# mistral_humtemp_breakout0.net
KiCad netlist of a schematic drawn in EAGLE
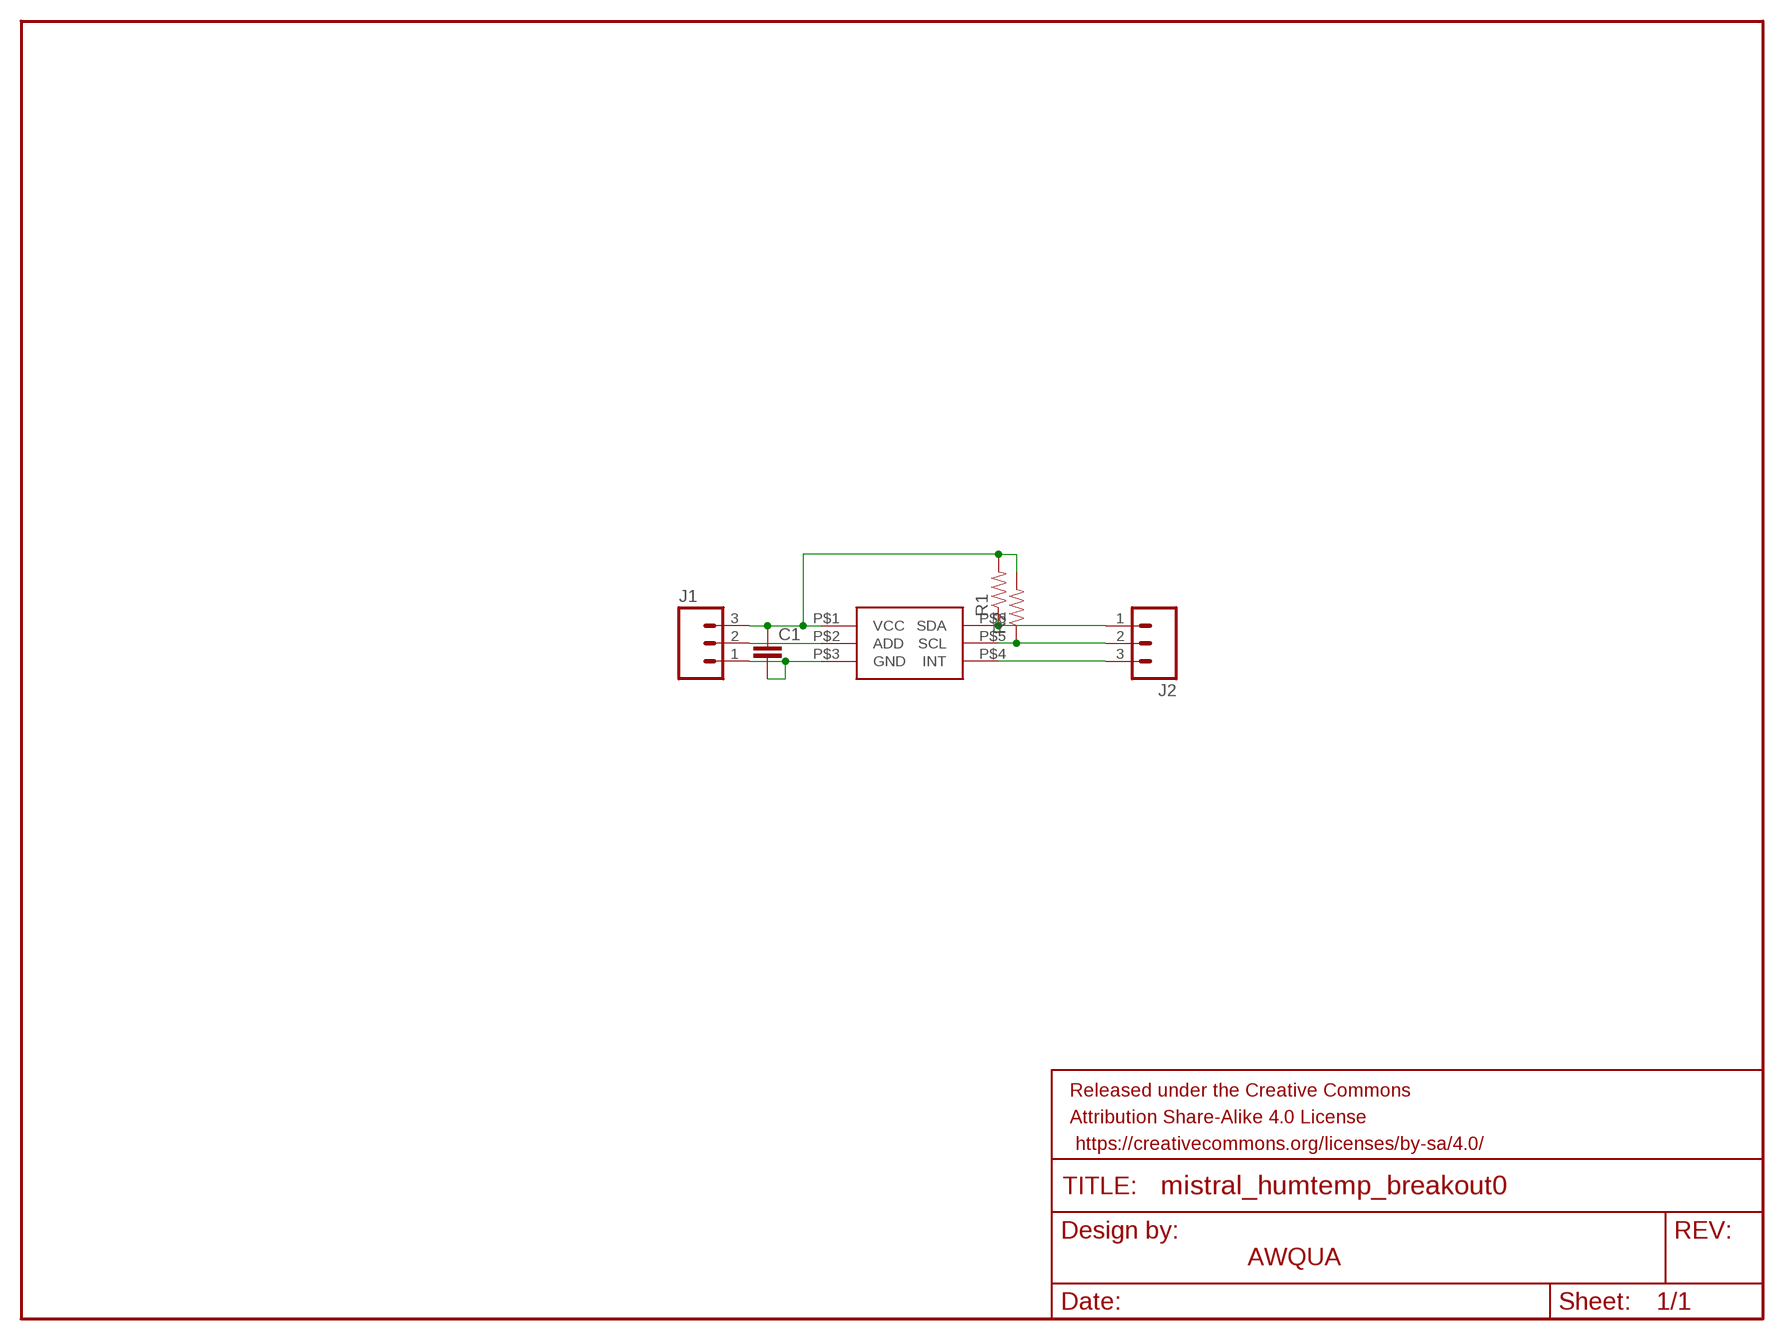
[diagram p0: schematic, sheet 1]

(export (version "E")
  (design (tool "Eeschema 10.0.6"))
  (components
    (comp (ref "C1")
      (value "CAP0603-CAP")
      (footprint "eagle-import:0603-CAP")
      (libsource (lib "eagle-import") (part "CAP0603-CAP"))
    )
    (comp (ref "FRAME1")
      (value "FRAME-LETTER")
      (footprint "eagle-import:CREATIVE_COMMONS")
      (libsource (lib "eagle-import") (part "FRAME-LETTER"))
    )
    (comp (ref "J1")
      (value "M03PTH")
      (footprint "eagle-import:1X03")
      (libsource (lib "eagle-import") (part "M03PTH"))
    )
    (comp (ref "J2")
      (value "M03PTH")
      (footprint "eagle-import:1X03")
      (libsource (lib "eagle-import") (part "M03PTH"))
    )
    (comp (ref "R1")
      (value "RESISTOR0603-RES")
      (footprint "eagle-import:0603-RES")
      (libsource (lib "eagle-import") (part "RESISTOR0603-RES"))
    )
    (comp (ref "R2")
      (value "RESISTOR0603-RES")
      (footprint "eagle-import:0603-RES")
      (libsource (lib "eagle-import") (part "RESISTOR0603-RES"))
    )
    (comp (ref "U$1")
      (value "HDC2010")
      (footprint "eagle-import:HDC2010")
      (libsource (lib "eagle-import") (part "HDC2010"))
    )
  )
  (nets
    (net (code "1") (name "Net-(U$1-ADD)") (class "Default")
      (node (ref "J1") (pin "2") (pinfunction "2_2") (pintype "passive"))
      (node (ref "U$1") (pin "P$2") (pinfunction "ADD_P$2") (pintype "bidirectional"))
    )
    (net (code "2") (name "Net-(U$1-GND)") (class "Default")
      (node (ref "C1") (pin "2") (pinfunction "2_2") (pintype "passive"))
      (node (ref "J1") (pin "1") (pinfunction "1_1") (pintype "passive"))
      (node (ref "U$1") (pin "P$3") (pinfunction "GND_P$3") (pintype "bidirectional"))
    )
    (net (code "3") (name "Net-(U$1-INT)") (class "Default")
      (node (ref "J2") (pin "3") (pinfunction "3_3") (pintype "passive"))
      (node (ref "U$1") (pin "P$4") (pinfunction "INT_P$4") (pintype "bidirectional"))
    )
    (net (code "4") (name "Net-(U$1-SCL)") (class "Default")
      (node (ref "J2") (pin "2") (pinfunction "2_2") (pintype "passive"))
      (node (ref "R2") (pin "1") (pinfunction "1_1") (pintype "passive"))
      (node (ref "U$1") (pin "P$5") (pinfunction "SCL_P$5") (pintype "bidirectional"))
    )
    (net (code "5") (name "Net-(U$1-SDA)") (class "Default")
      (node (ref "J2") (pin "1") (pinfunction "1_1") (pintype "passive"))
      (node (ref "R1") (pin "1") (pinfunction "1_1") (pintype "passive"))
      (node (ref "U$1") (pin "P$6") (pinfunction "SDA_P$6") (pintype "bidirectional"))
    )
    (net (code "6") (name "Net-(U$1-VCC)") (class "Default")
      (node (ref "C1") (pin "1") (pinfunction "1_1") (pintype "passive"))
      (node (ref "J1") (pin "3") (pinfunction "3_3") (pintype "passive"))
      (node (ref "R1") (pin "2") (pinfunction "2_2") (pintype "passive"))
      (node (ref "R2") (pin "2") (pinfunction "2_2") (pintype "passive"))
      (node (ref "U$1") (pin "P$1") (pinfunction "VCC_P$1") (pintype "bidirectional"))
    )
  )
)
